# Interconnect.net
KiCad netlist of a schematic drawn in Altium Designer
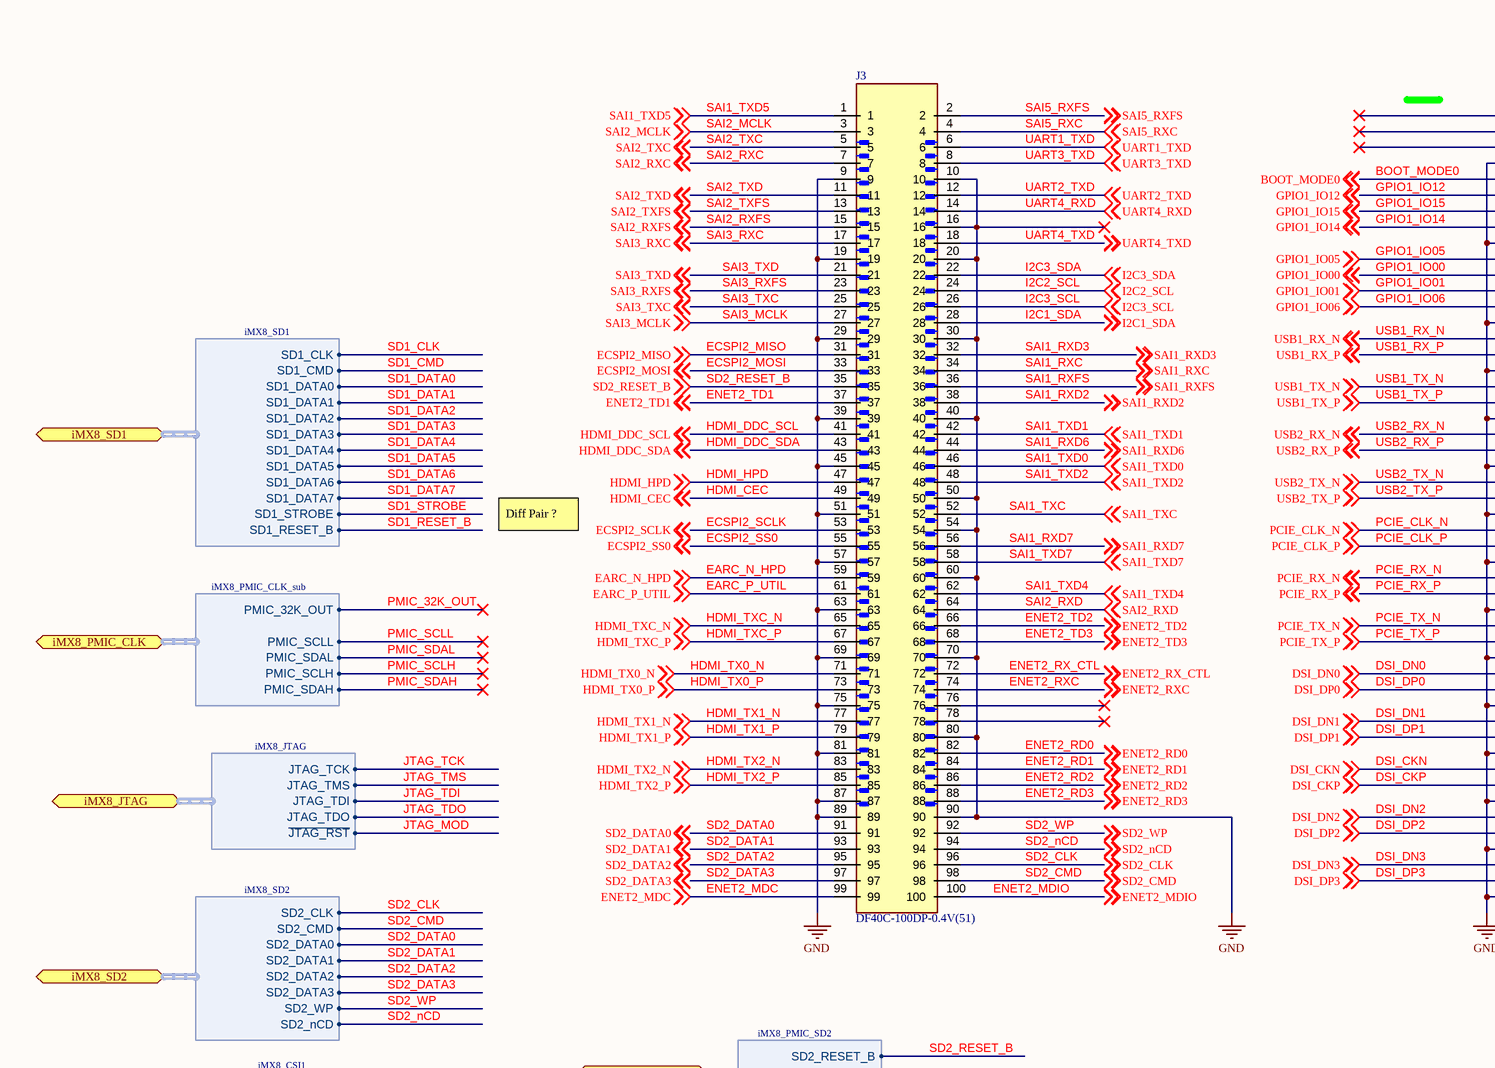
[diagram p0: Interconnect.SchDoc, top left]
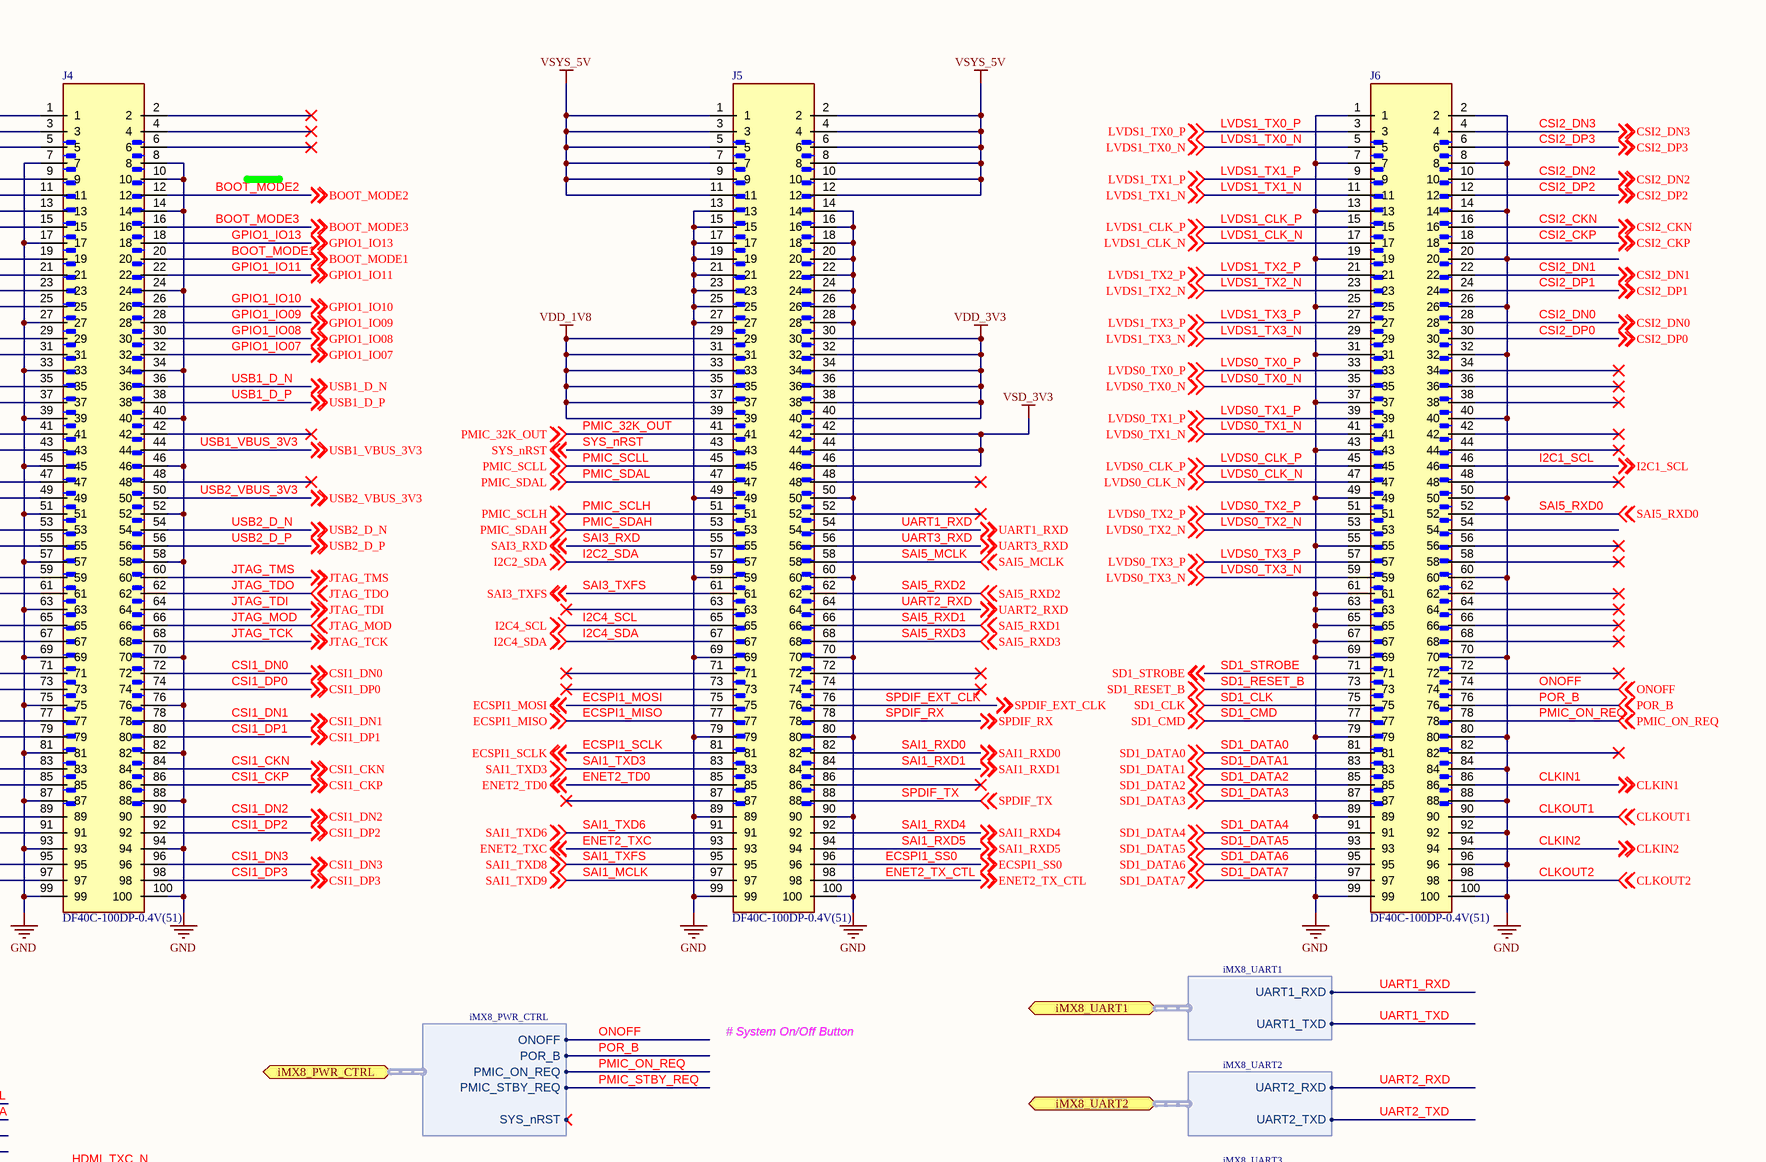
[diagram p1: Interconnect.SchDoc, top right]
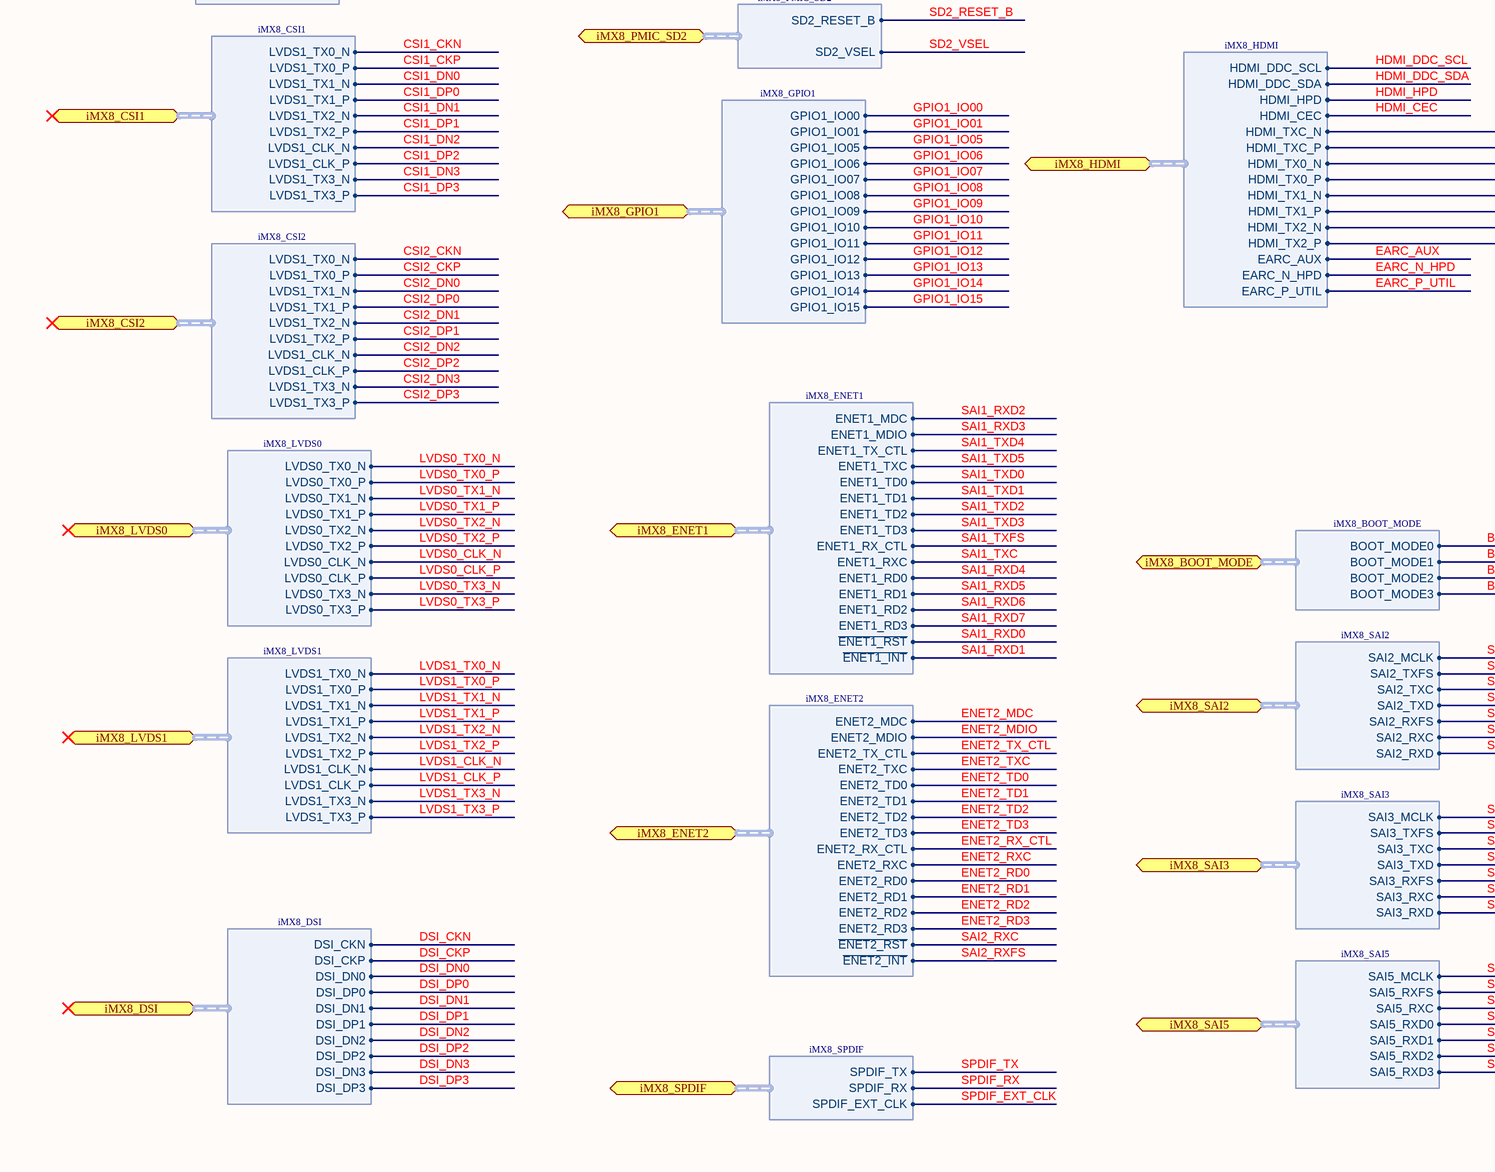
[diagram p2: Interconnect.SchDoc, bottom left]
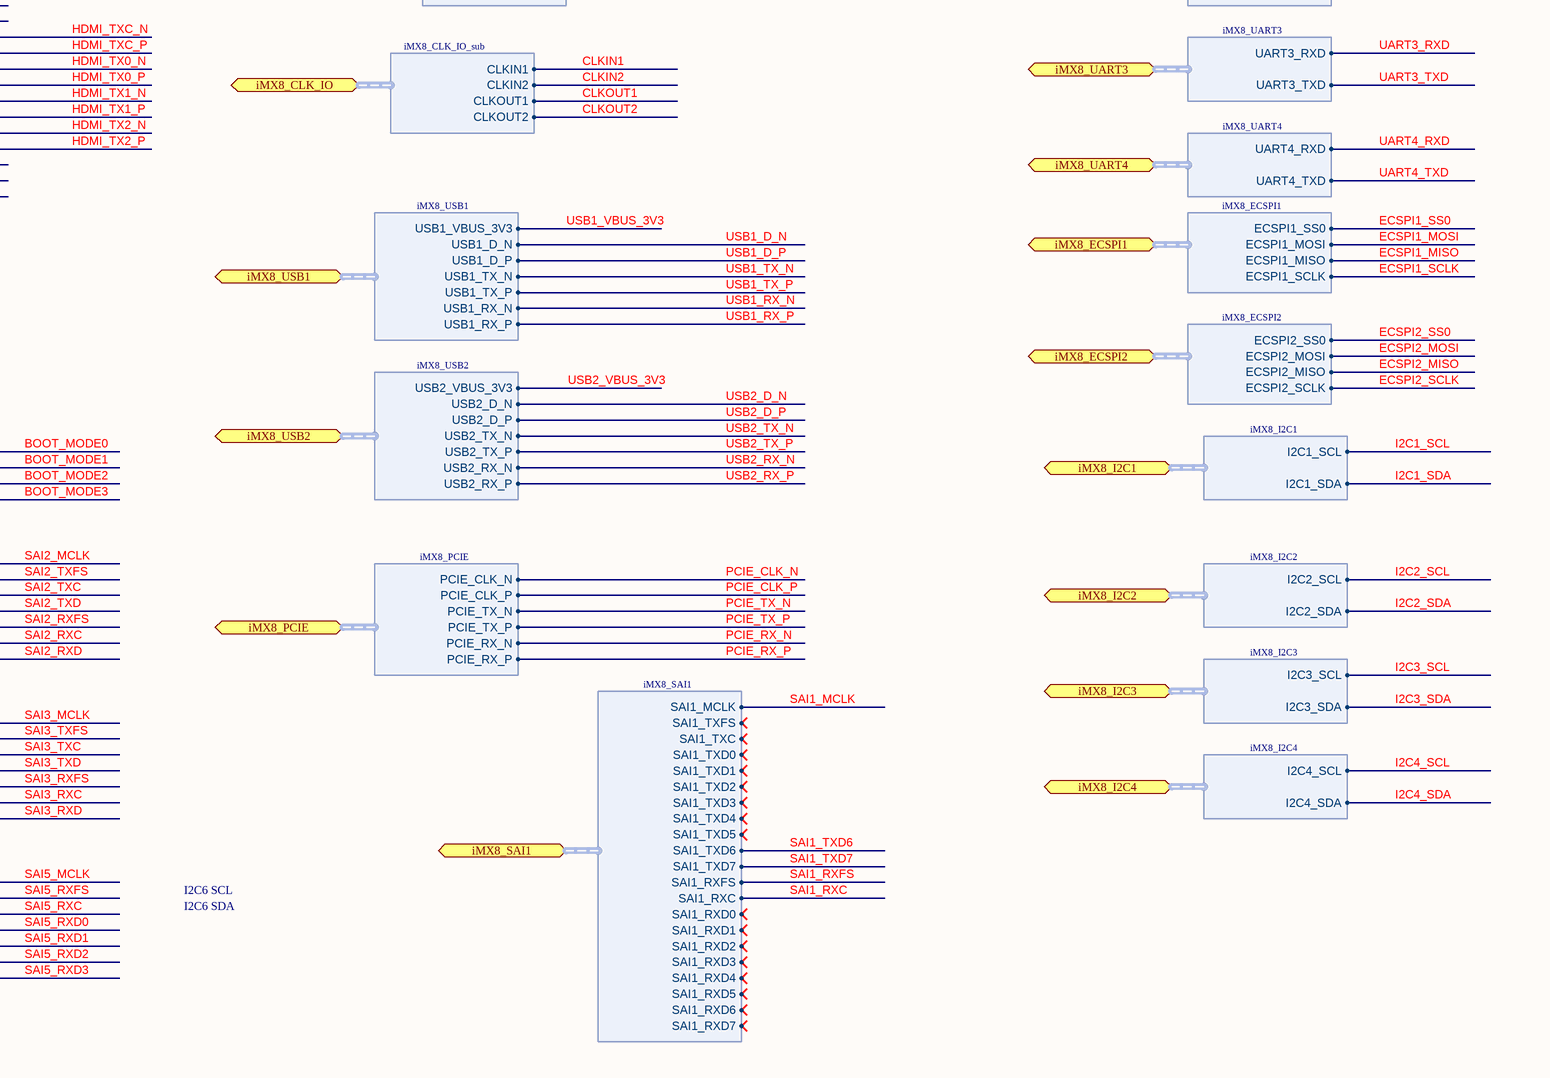
[diagram p3: Interconnect.SchDoc, bottom right]

(export (version "E")
  (design (tool "Eeschema 10.0.6"))
  (components
    (comp (ref "J3")
      (value "DF40C-100DP-0.4V(51)")
      (footprint "HIROSE_DF40C-100DP-0.4V(51)")
      (description "100 Position Connector Plug, Outer Shroud Contacts Surface Mount Gold")
      (fields (field (name "MF") "Hirose Electric"))
      (libsource (lib "DF40C-100DP-0.4V_51_") (part "DF40C-100DP-0.4V(51)"))
    )
    (comp (ref "J4")
      (value "DF40C-100DP-0.4V(51)")
      (footprint "HIROSE_DF40C-100DP-0.4V(51)")
      (description "100 Position Connector Plug, Outer Shroud Contacts Surface Mount Gold")
      (fields (field (name "MF") "Hirose Electric"))
      (libsource (lib "DF40C-100DP-0.4V_51_") (part "DF40C-100DP-0.4V(51)"))
    )
    (comp (ref "J5")
      (value "DF40C-100DP-0.4V(51)")
      (footprint "HIROSE_DF40C-100DP-0.4V(51)")
      (description "100 Position Connector Plug, Outer Shroud Contacts Surface Mount Gold")
      (fields (field (name "MF") "Hirose Electric"))
      (libsource (lib "DF40C-100DP-0.4V_51_") (part "DF40C-100DP-0.4V(51)"))
    )
    (comp (ref "J6")
      (value "DF40C-100DP-0.4V(51)")
      (footprint "HIROSE_DF40C-100DP-0.4V(51)")
      (description "100 Position Connector Plug, Outer Shroud Contacts Surface Mount Gold")
      (fields (field (name "MF") "Hirose Electric"))
      (libsource (lib "DF40C-100DP-0.4V_51_") (part "DF40C-100DP-0.4V(51)"))
    )
  )
  (nets
    (net (code "74") (name "BOOT_MODE0") (class "Default")
      (node (ref "J4") (pin "9") (pinfunction "9_9") (pintype "passive"))
    )
    (net (code "75") (name "BOOT_MODE1") (class "Default")
      (node (ref "J4") (pin "20") (pinfunction "20_20") (pintype "passive"))
    )
    (net (code "76") (name "BOOT_MODE2") (class "Default")
      (node (ref "J4") (pin "12") (pinfunction "12_12") (pintype "passive"))
    )
    (net (code "77") (name "BOOT_MODE3") (class "Default")
      (node (ref "J4") (pin "16") (pinfunction "16_16") (pintype "passive"))
    )
    (net (code "78") (name "CLKIN1") (class "Default")
      (node (ref "J6") (pin "86") (pinfunction "86_86") (pintype "passive"))
    )
    (net (code "79") (name "CLKIN2") (class "Default")
      (node (ref "J6") (pin "94") (pinfunction "94_94") (pintype "passive"))
    )
    (net (code "80") (name "CLKOUT1") (class "Default")
      (node (ref "J6") (pin "90") (pinfunction "90_90") (pintype "passive"))
    )
    (net (code "81") (name "CLKOUT2") (class "Default")
      (node (ref "J6") (pin "98") (pinfunction "98_98") (pintype "passive"))
    )
    (net (code "82") (name "CSI1_CKN") (class "Default")
      (node (ref "J4") (pin "84") (pinfunction "84_84") (pintype "passive"))
    )
    (net (code "83") (name "CSI1_CKP") (class "Default")
      (node (ref "J4") (pin "86") (pinfunction "86_86") (pintype "passive"))
    )
    (net (code "84") (name "CSI1_DN0") (class "Default")
      (node (ref "J4") (pin "72") (pinfunction "72_72") (pintype "passive"))
    )
    (net (code "85") (name "CSI1_DN1") (class "Default")
      (node (ref "J4") (pin "78") (pinfunction "78_78") (pintype "passive"))
    )
    (net (code "86") (name "CSI1_DN2") (class "Default")
      (node (ref "J4") (pin "90") (pinfunction "90_90") (pintype "passive"))
    )
    (net (code "87") (name "CSI1_DN3") (class "Default")
      (node (ref "J4") (pin "96") (pinfunction "96_96") (pintype "passive"))
    )
    (net (code "88") (name "CSI1_DP0") (class "Default")
      (node (ref "J4") (pin "74") (pinfunction "74_74") (pintype "passive"))
    )
    (net (code "89") (name "CSI1_DP1") (class "Default")
      (node (ref "J4") (pin "80") (pinfunction "80_80") (pintype "passive"))
    )
    (net (code "90") (name "CSI1_DP2") (class "Default")
      (node (ref "J4") (pin "92") (pinfunction "92_92") (pintype "passive"))
    )
    (net (code "91") (name "CSI1_DP3") (class "Default")
      (node (ref "J4") (pin "98") (pinfunction "98_98") (pintype "passive"))
    )
    (net (code "92") (name "CSI2_CKN") (class "Default")
      (node (ref "J6") (pin "16") (pinfunction "16_16") (pintype "passive"))
    )
    (net (code "93") (name "CSI2_CKP") (class "Default")
      (node (ref "J6") (pin "18") (pinfunction "18_18") (pintype "passive"))
    )
    (net (code "94") (name "CSI2_DN0") (class "Default")
      (node (ref "J6") (pin "28") (pinfunction "28_28") (pintype "passive"))
    )
    (net (code "95") (name "CSI2_DN1") (class "Default")
      (node (ref "J6") (pin "22") (pinfunction "22_22") (pintype "passive"))
    )
    (net (code "96") (name "CSI2_DN2") (class "Default")
      (node (ref "J6") (pin "10") (pinfunction "10_10") (pintype "passive"))
    )
    (net (code "97") (name "CSI2_DN3") (class "Default")
      (node (ref "J6") (pin "4") (pinfunction "4_4") (pintype "passive"))
    )
    (net (code "98") (name "CSI2_DP0") (class "Default")
      (node (ref "J6") (pin "30") (pinfunction "30_30") (pintype "passive"))
    )
    (net (code "99") (name "CSI2_DP1") (class "Default")
      (node (ref "J6") (pin "24") (pinfunction "24_24") (pintype "passive"))
    )
    (net (code "100") (name "CSI2_DP2") (class "Default")
      (node (ref "J6") (pin "12") (pinfunction "12_12") (pintype "passive"))
    )
    (net (code "101") (name "CSI2_DP3") (class "Default")
      (node (ref "J6") (pin "6") (pinfunction "6_6") (pintype "passive"))
    )
    (net (code "102") (name "DSI_CKN") (class "Default")
      (node (ref "J4") (pin "83") (pinfunction "83_83") (pintype "passive"))
    )
    (net (code "103") (name "DSI_CKP") (class "Default")
      (node (ref "J4") (pin "85") (pinfunction "85_85") (pintype "passive"))
    )
    (net (code "104") (name "DSI_DN0") (class "Default")
      (node (ref "J4") (pin "71") (pinfunction "71_71") (pintype "passive"))
    )
    (net (code "105") (name "DSI_DN1") (class "Default")
      (node (ref "J4") (pin "77") (pinfunction "77_77") (pintype "passive"))
    )
    (net (code "106") (name "DSI_DN2") (class "Default")
      (node (ref "J4") (pin "89") (pinfunction "89_89") (pintype "passive"))
    )
    (net (code "107") (name "DSI_DN3") (class "Default")
      (node (ref "J4") (pin "95") (pinfunction "95_95") (pintype "passive"))
    )
    (net (code "108") (name "DSI_DP0") (class "Default")
      (node (ref "J4") (pin "73") (pinfunction "73_73") (pintype "passive"))
    )
    (net (code "109") (name "DSI_DP1") (class "Default")
      (node (ref "J4") (pin "79") (pinfunction "79_79") (pintype "passive"))
    )
    (net (code "110") (name "DSI_DP2") (class "Default")
      (node (ref "J4") (pin "91") (pinfunction "91_91") (pintype "passive"))
    )
    (net (code "111") (name "DSI_DP3") (class "Default")
      (node (ref "J4") (pin "97") (pinfunction "97_97") (pintype "passive"))
    )
    (net (code "112") (name "EARC_N_HPD") (class "Default")
      (node (ref "J3") (pin "59") (pinfunction "59_59") (pintype "passive"))
    )
    (net (code "113") (name "EARC_P_UTIL") (class "Default")
      (node (ref "J3") (pin "61") (pinfunction "61_61") (pintype "passive"))
    )
    (net (code "114") (name "ECSPI1_MISO") (class "Default")
      (node (ref "J5") (pin "77") (pinfunction "77_77") (pintype "passive"))
    )
    (net (code "115") (name "ECSPI1_MOSI") (class "Default")
      (node (ref "J5") (pin "75") (pinfunction "75_75") (pintype "passive"))
    )
    (net (code "116") (name "ECSPI1_SCLK") (class "Default")
      (node (ref "J5") (pin "81") (pinfunction "81_81") (pintype "passive"))
    )
    (net (code "117") (name "ECSPI1_SS0") (class "Default")
      (node (ref "J5") (pin "96") (pinfunction "96_96") (pintype "passive"))
    )
    (net (code "118") (name "ECSPI2_MISO") (class "Default")
      (node (ref "J3") (pin "31") (pinfunction "31_31") (pintype "passive"))
    )
    (net (code "119") (name "ECSPI2_MOSI") (class "Default")
      (node (ref "J3") (pin "33") (pinfunction "33_33") (pintype "passive"))
    )
    (net (code "120") (name "ECSPI2_SCLK") (class "Default")
      (node (ref "J3") (pin "53") (pinfunction "53_53") (pintype "passive"))
    )
    (net (code "121") (name "ECSPI2_SS0") (class "Default")
      (node (ref "J3") (pin "55") (pinfunction "55_55") (pintype "passive"))
    )
    (net (code "122") (name "ENET2_MDC") (class "Default")
      (node (ref "J3") (pin "99") (pinfunction "99_99") (pintype "passive"))
    )
    (net (code "123") (name "ENET2_MDIO") (class "Default")
      (node (ref "J3") (pin "100") (pinfunction "100_100") (pintype "passive"))
    )
    (net (code "124") (name "ENET2_RD0") (class "Default")
      (node (ref "J3") (pin "82") (pinfunction "82_82") (pintype "passive"))
    )
    (net (code "125") (name "ENET2_RD1") (class "Default")
      (node (ref "J3") (pin "84") (pinfunction "84_84") (pintype "passive"))
    )
    (net (code "126") (name "ENET2_RD2") (class "Default")
      (node (ref "J3") (pin "86") (pinfunction "86_86") (pintype "passive"))
    )
    (net (code "127") (name "ENET2_RD3") (class "Default")
      (node (ref "J3") (pin "88") (pinfunction "88_88") (pintype "passive"))
    )
    (net (code "128") (name "ENET2_RXC") (class "Default")
      (node (ref "J3") (pin "74") (pinfunction "74_74") (pintype "passive"))
    )
    (net (code "129") (name "ENET2_RX_CTL") (class "Default")
      (node (ref "J3") (pin "72") (pinfunction "72_72") (pintype "passive"))
    )
    (net (code "130") (name "ENET2_TD0") (class "Default")
      (node (ref "J5") (pin "85") (pinfunction "85_85") (pintype "passive"))
    )
    (net (code "131") (name "ENET2_TD1") (class "Default")
      (node (ref "J3") (pin "37") (pinfunction "37_37") (pintype "passive"))
    )
    (net (code "132") (name "ENET2_TD2") (class "Default")
      (node (ref "J3") (pin "66") (pinfunction "66_66") (pintype "passive"))
    )
    (net (code "133") (name "ENET2_TD3") (class "Default")
      (node (ref "J3") (pin "68") (pinfunction "68_68") (pintype "passive"))
    )
    (net (code "134") (name "ENET2_TXC") (class "Default")
      (node (ref "J5") (pin "93") (pinfunction "93_93") (pintype "passive"))
    )
    (net (code "135") (name "ENET2_TX_CTL") (class "Default")
      (node (ref "J5") (pin "98") (pinfunction "98_98") (pintype "passive"))
    )
    (net (code "136") (name "GND") (class "Default")
      (node (ref "J3") (pin "10") (pinfunction "10_10") (pintype "passive"))
      (node (ref "J3") (pin "16") (pinfunction "16_16") (pintype "passive"))
      (node (ref "J3") (pin "19") (pinfunction "19_19") (pintype "passive"))
      (node (ref "J3") (pin "20") (pinfunction "20_20") (pintype "passive"))
      (node (ref "J3") (pin "29") (pinfunction "29_29") (pintype "passive"))
      (node (ref "J3") (pin "30") (pinfunction "30_30") (pintype "passive"))
      (node (ref "J3") (pin "39") (pinfunction "39_39") (pintype "passive"))
      (node (ref "J3") (pin "40") (pinfunction "40_40") (pintype "passive"))
      (node (ref "J3") (pin "45") (pinfunction "45_45") (pintype "passive"))
      (node (ref "J3") (pin "50") (pinfunction "50_50") (pintype "passive"))
      (node (ref "J3") (pin "51") (pinfunction "51_51") (pintype "passive"))
      (node (ref "J3") (pin "54") (pinfunction "54_54") (pintype "passive"))
      (node (ref "J3") (pin "57") (pinfunction "57_57") (pintype "passive"))
      (node (ref "J3") (pin "60") (pinfunction "60_60") (pintype "passive"))
      (node (ref "J3") (pin "63") (pinfunction "63_63") (pintype "passive"))
      (node (ref "J3") (pin "69") (pinfunction "69_69") (pintype "passive"))
      (node (ref "J3") (pin "70") (pinfunction "70_70") (pintype "passive"))
      (node (ref "J3") (pin "75") (pinfunction "75_75") (pintype "passive"))
      (node (ref "J3") (pin "80") (pinfunction "80_80") (pintype "passive"))
      (node (ref "J3") (pin "81") (pinfunction "81_81") (pintype "passive"))
      (node (ref "J3") (pin "87") (pinfunction "87_87") (pintype "passive"))
      (node (ref "J3") (pin "89") (pinfunction "89_89") (pintype "passive"))
      (node (ref "J3") (pin "9") (pinfunction "9_9") (pintype "passive"))
      (node (ref "J3") (pin "90") (pinfunction "90_90") (pintype "passive"))
      (node (ref "J4") (pin "10") (pinfunction "10_10") (pintype "passive"))
      (node (ref "J4") (pin "100") (pinfunction "100_100") (pintype "passive"))
      (node (ref "J4") (pin "14") (pinfunction "14_14") (pintype "passive"))
      (node (ref "J4") (pin "17") (pinfunction "17_17") (pintype "passive"))
      (node (ref "J4") (pin "24") (pinfunction "24_24") (pintype "passive"))
      (node (ref "J4") (pin "27") (pinfunction "27_27") (pintype "passive"))
      (node (ref "J4") (pin "33") (pinfunction "33_33") (pintype "passive"))
      (node (ref "J4") (pin "34") (pinfunction "34_34") (pintype "passive"))
      (node (ref "J4") (pin "39") (pinfunction "39_39") (pintype "passive"))
      (node (ref "J4") (pin "40") (pinfunction "40_40") (pintype "passive"))
      (node (ref "J4") (pin "45") (pinfunction "45_45") (pintype "passive"))
      (node (ref "J4") (pin "46") (pinfunction "46_46") (pintype "passive"))
      (node (ref "J4") (pin "51") (pinfunction "51_51") (pintype "passive"))
      (node (ref "J4") (pin "52") (pinfunction "52_52") (pintype "passive"))
      (node (ref "J4") (pin "57") (pinfunction "57_57") (pintype "passive"))
      (node (ref "J4") (pin "58") (pinfunction "58_58") (pintype "passive"))
      (node (ref "J4") (pin "63") (pinfunction "63_63") (pintype "passive"))
      (node (ref "J4") (pin "69") (pinfunction "69_69") (pintype "passive"))
      (node (ref "J4") (pin "7") (pinfunction "7_7") (pintype "passive"))
      (node (ref "J4") (pin "70") (pinfunction "70_70") (pintype "passive"))
      (node (ref "J4") (pin "75") (pinfunction "75_75") (pintype "passive"))
      (node (ref "J4") (pin "76") (pinfunction "76_76") (pintype "passive"))
      (node (ref "J4") (pin "8") (pinfunction "8_8") (pintype "passive"))
      (node (ref "J4") (pin "81") (pinfunction "81_81") (pintype "passive"))
      (node (ref "J4") (pin "82") (pinfunction "82_82") (pintype "passive"))
      (node (ref "J4") (pin "87") (pinfunction "87_87") (pintype "passive"))
      (node (ref "J4") (pin "88") (pinfunction "88_88") (pintype "passive"))
      (node (ref "J4") (pin "93") (pinfunction "93_93") (pintype "passive"))
      (node (ref "J4") (pin "94") (pinfunction "94_94") (pintype "passive"))
      (node (ref "J4") (pin "99") (pinfunction "99_99") (pintype "passive"))
      (node (ref "J5") (pin "100") (pinfunction "100_100") (pintype "passive"))
      (node (ref "J5") (pin "13") (pinfunction "13_13") (pintype "passive"))
      (node (ref "J5") (pin "14") (pinfunction "14_14") (pintype "passive"))
      (node (ref "J5") (pin "15") (pinfunction "15_15") (pintype "passive"))
      (node (ref "J5") (pin "16") (pinfunction "16_16") (pintype "passive"))
      (node (ref "J5") (pin "17") (pinfunction "17_17") (pintype "passive"))
      (node (ref "J5") (pin "18") (pinfunction "18_18") (pintype "passive"))
      (node (ref "J5") (pin "19") (pinfunction "19_19") (pintype "passive"))
      (node (ref "J5") (pin "20") (pinfunction "20_20") (pintype "passive"))
      (node (ref "J5") (pin "21") (pinfunction "21_21") (pintype "passive"))
      (node (ref "J5") (pin "22") (pinfunction "22_22") (pintype "passive"))
      (node (ref "J5") (pin "23") (pinfunction "23_23") (pintype "passive"))
      (node (ref "J5") (pin "24") (pinfunction "24_24") (pintype "passive"))
      (node (ref "J5") (pin "25") (pinfunction "25_25") (pintype "passive"))
      (node (ref "J5") (pin "26") (pinfunction "26_26") (pintype "passive"))
      (node (ref "J5") (pin "27") (pinfunction "27_27") (pintype "passive"))
      (node (ref "J5") (pin "28") (pinfunction "28_28") (pintype "passive"))
      (node (ref "J5") (pin "49") (pinfunction "49_49") (pintype "passive"))
      (node (ref "J5") (pin "50") (pinfunction "50_50") (pintype "passive"))
      (node (ref "J5") (pin "59") (pinfunction "59_59") (pintype "passive"))
      (node (ref "J5") (pin "60") (pinfunction "60_60") (pintype "passive"))
      (node (ref "J5") (pin "69") (pinfunction "69_69") (pintype "passive"))
      (node (ref "J5") (pin "70") (pinfunction "70_70") (pintype "passive"))
      (node (ref "J5") (pin "79") (pinfunction "79_79") (pintype "passive"))
      (node (ref "J5") (pin "80") (pinfunction "80_80") (pintype "passive"))
      (node (ref "J5") (pin "89") (pinfunction "89_89") (pintype "passive"))
      (node (ref "J5") (pin "90") (pinfunction "90_90") (pintype "passive"))
      (node (ref "J5") (pin "99") (pinfunction "99_99") (pintype "passive"))
      (node (ref "J6") (pin "1") (pinfunction "1_1") (pintype "passive"))
      (node (ref "J6") (pin "100") (pinfunction "100_100") (pintype "passive"))
      (node (ref "J6") (pin "13") (pinfunction "13_13") (pintype "passive"))
      (node (ref "J6") (pin "14") (pinfunction "14_14") (pintype "passive"))
      (node (ref "J6") (pin "19") (pinfunction "19_19") (pintype "passive"))
      (node (ref "J6") (pin "2") (pinfunction "2_2") (pintype "passive"))
      (node (ref "J6") (pin "20") (pinfunction "20_20") (pintype "passive"))
      (node (ref "J6") (pin "25") (pinfunction "25_25") (pintype "passive"))
      (node (ref "J6") (pin "26") (pinfunction "26_26") (pintype "passive"))
      (node (ref "J6") (pin "31") (pinfunction "31_31") (pintype "passive"))
      (node (ref "J6") (pin "32") (pinfunction "32_32") (pintype "passive"))
      (node (ref "J6") (pin "37") (pinfunction "37_37") (pintype "passive"))
      (node (ref "J6") (pin "40") (pinfunction "40_40") (pintype "passive"))
      (node (ref "J6") (pin "43") (pinfunction "43_43") (pintype "passive"))
      (node (ref "J6") (pin "49") (pinfunction "49_49") (pintype "passive"))
      (node (ref "J6") (pin "50") (pinfunction "50_50") (pintype "passive"))
      (node (ref "J6") (pin "55") (pinfunction "55_55") (pintype "passive"))
      (node (ref "J6") (pin "60") (pinfunction "60_60") (pintype "passive"))
      (node (ref "J6") (pin "61") (pinfunction "61_61") (pintype "passive"))
      (node (ref "J6") (pin "63") (pinfunction "63_63") (pintype "passive"))
      (node (ref "J6") (pin "65") (pinfunction "65_65") (pintype "passive"))
      (node (ref "J6") (pin "67") (pinfunction "67_67") (pintype "passive"))
      (node (ref "J6") (pin "69") (pinfunction "69_69") (pintype "passive"))
      (node (ref "J6") (pin "7") (pinfunction "7_7") (pintype "passive"))
      (node (ref "J6") (pin "70") (pinfunction "70_70") (pintype "passive"))
      (node (ref "J6") (pin "79") (pinfunction "79_79") (pintype "passive"))
      (node (ref "J6") (pin "8") (pinfunction "8_8") (pintype "passive"))
      (node (ref "J6") (pin "80") (pinfunction "80_80") (pintype "passive"))
      (node (ref "J6") (pin "84") (pinfunction "84_84") (pintype "passive"))
      (node (ref "J6") (pin "88") (pinfunction "88_88") (pintype "passive"))
      (node (ref "J6") (pin "89") (pinfunction "89_89") (pintype "passive"))
      (node (ref "J6") (pin "92") (pinfunction "92_92") (pintype "passive"))
      (node (ref "J6") (pin "96") (pinfunction "96_96") (pintype "passive"))
      (node (ref "J6") (pin "99") (pinfunction "99_99") (pintype "passive"))
    )
    (net (code "137") (name "GPIO1_IO00") (class "Default")
      (node (ref "J4") (pin "21") (pinfunction "21_21") (pintype "passive"))
    )
    (net (code "138") (name "GPIO1_IO01") (class "Default")
      (node (ref "J4") (pin "23") (pinfunction "23_23") (pintype "passive"))
    )
    (net (code "139") (name "GPIO1_IO05") (class "Default")
      (node (ref "J4") (pin "19") (pinfunction "19_19") (pintype "passive"))
    )
    (net (code "140") (name "GPIO1_IO06") (class "Default")
      (node (ref "J4") (pin "25") (pinfunction "25_25") (pintype "passive"))
    )
    (net (code "141") (name "GPIO1_IO07") (class "Default")
      (node (ref "J4") (pin "32") (pinfunction "32_32") (pintype "passive"))
    )
    (net (code "142") (name "GPIO1_IO08") (class "Default")
      (node (ref "J4") (pin "30") (pinfunction "30_30") (pintype "passive"))
    )
    (net (code "143") (name "GPIO1_IO09") (class "Default")
      (node (ref "J4") (pin "28") (pinfunction "28_28") (pintype "passive"))
    )
    (net (code "144") (name "GPIO1_IO10") (class "Default")
      (node (ref "J4") (pin "26") (pinfunction "26_26") (pintype "passive"))
    )
    (net (code "145") (name "GPIO1_IO11") (class "Default")
      (node (ref "J4") (pin "22") (pinfunction "22_22") (pintype "passive"))
    )
    (net (code "146") (name "GPIO1_IO12") (class "Default")
      (node (ref "J4") (pin "11") (pinfunction "11_11") (pintype "passive"))
    )
    (net (code "147") (name "GPIO1_IO13") (class "Default")
      (node (ref "J4") (pin "18") (pinfunction "18_18") (pintype "passive"))
    )
    (net (code "148") (name "GPIO1_IO14") (class "Default")
      (node (ref "J4") (pin "15") (pinfunction "15_15") (pintype "passive"))
    )
    (net (code "149") (name "GPIO1_IO15") (class "Default")
      (node (ref "J4") (pin "13") (pinfunction "13_13") (pintype "passive"))
    )
    (net (code "150") (name "HDMI_CEC") (class "Default")
      (node (ref "J3") (pin "49") (pinfunction "49_49") (pintype "passive"))
    )
    (net (code "151") (name "HDMI_DDC_SCL") (class "Default")
      (node (ref "J3") (pin "41") (pinfunction "41_41") (pintype "passive"))
    )
    (net (code "152") (name "HDMI_DDC_SDA") (class "Default")
      (node (ref "J3") (pin "43") (pinfunction "43_43") (pintype "passive"))
    )
    (net (code "153") (name "HDMI_HPD") (class "Default")
      (node (ref "J3") (pin "47") (pinfunction "47_47") (pintype "passive"))
    )
    (net (code "154") (name "HDMI_TX0_N") (class "Default")
      (node (ref "J3") (pin "71") (pinfunction "71_71") (pintype "passive"))
    )
    (net (code "155") (name "HDMI_TX0_P") (class "Default")
      (node (ref "J3") (pin "73") (pinfunction "73_73") (pintype "passive"))
    )
    (net (code "156") (name "HDMI_TX1_N") (class "Default")
      (node (ref "J3") (pin "77") (pinfunction "77_77") (pintype "passive"))
    )
    (net (code "157") (name "HDMI_TX1_P") (class "Default")
      (node (ref "J3") (pin "79") (pinfunction "79_79") (pintype "passive"))
    )
    (net (code "158") (name "HDMI_TX2_N") (class "Default")
      (node (ref "J3") (pin "83") (pinfunction "83_83") (pintype "passive"))
    )
    (net (code "159") (name "HDMI_TX2_P") (class "Default")
      (node (ref "J3") (pin "85") (pinfunction "85_85") (pintype "passive"))
    )
    (net (code "160") (name "HDMI_TXC_N") (class "Default")
      (node (ref "J3") (pin "65") (pinfunction "65_65") (pintype "passive"))
    )
    (net (code "161") (name "HDMI_TXC_P") (class "Default")
      (node (ref "J3") (pin "67") (pinfunction "67_67") (pintype "passive"))
    )
    (net (code "162") (name "I2C1_SCL") (class "Default")
      (node (ref "J6") (pin "46") (pinfunction "46_46") (pintype "passive"))
    )
    (net (code "163") (name "I2C1_SDA") (class "Default")
      (node (ref "J3") (pin "28") (pinfunction "28_28") (pintype "passive"))
    )
    (net (code "164") (name "I2C2_SCL") (class "Default")
      (node (ref "J3") (pin "24") (pinfunction "24_24") (pintype "passive"))
    )
    (net (code "165") (name "I2C2_SDA") (class "Default")
      (node (ref "J5") (pin "57") (pinfunction "57_57") (pintype "passive"))
    )
    (net (code "166") (name "I2C3_SCL") (class "Default")
      (node (ref "J3") (pin "26") (pinfunction "26_26") (pintype "passive"))
    )
    (net (code "167") (name "I2C3_SDA") (class "Default")
      (node (ref "J3") (pin "22") (pinfunction "22_22") (pintype "passive"))
    )
    (net (code "168") (name "I2C4_SCL") (class "Default")
      (node (ref "J5") (pin "65") (pinfunction "65_65") (pintype "passive"))
    )
    (net (code "169") (name "I2C4_SDA") (class "Default")
      (node (ref "J5") (pin "67") (pinfunction "67_67") (pintype "passive"))
    )
    (net (code "170") (name "JTAG_MOD") (class "Default")
      (node (ref "J4") (pin "66") (pinfunction "66_66") (pintype "passive"))
    )
    (net (code "171") (name "JTAG_TCK") (class "Default")
      (node (ref "J4") (pin "68") (pinfunction "68_68") (pintype "passive"))
    )
    (net (code "172") (name "JTAG_TDI") (class "Default")
      (node (ref "J4") (pin "64") (pinfunction "64_64") (pintype "passive"))
    )
    (net (code "173") (name "JTAG_TDO") (class "Default")
      (node (ref "J4") (pin "62") (pinfunction "62_62") (pintype "passive"))
    )
    (net (code "174") (name "JTAG_TMS") (class "Default")
      (node (ref "J4") (pin "60") (pinfunction "60_60") (pintype "passive"))
    )
    (net (code "175") (name "LVDS0_CLK_N") (class "Default")
      (node (ref "J6") (pin "47") (pinfunction "47_47") (pintype "passive"))
    )
    (net (code "176") (name "LVDS0_CLK_P") (class "Default")
      (node (ref "J6") (pin "45") (pinfunction "45_45") (pintype "passive"))
    )
    (net (code "177") (name "LVDS0_TX0_N") (class "Default")
      (node (ref "J6") (pin "35") (pinfunction "35_35") (pintype "passive"))
    )
    (net (code "178") (name "LVDS0_TX0_P") (class "Default")
      (node (ref "J6") (pin "33") (pinfunction "33_33") (pintype "passive"))
    )
    (net (code "179") (name "LVDS0_TX1_N") (class "Default")
      (node (ref "J6") (pin "41") (pinfunction "41_41") (pintype "passive"))
    )
    (net (code "180") (name "LVDS0_TX1_P") (class "Default")
      (node (ref "J6") (pin "39") (pinfunction "39_39") (pintype "passive"))
    )
    (net (code "181") (name "LVDS0_TX2_N") (class "Default")
      (node (ref "J6") (pin "53") (pinfunction "53_53") (pintype "passive"))
    )
    (net (code "182") (name "LVDS0_TX2_P") (class "Default")
      (node (ref "J6") (pin "51") (pinfunction "51_51") (pintype "passive"))
    )
    (net (code "183") (name "LVDS0_TX3_N") (class "Default")
      (node (ref "J6") (pin "59") (pinfunction "59_59") (pintype "passive"))
    )
    (net (code "184") (name "LVDS0_TX3_P") (class "Default")
      (node (ref "J6") (pin "57") (pinfunction "57_57") (pintype "passive"))
    )
    (net (code "185") (name "LVDS1_CLK_N") (class "Default")
      (node (ref "J6") (pin "17") (pinfunction "17_17") (pintype "passive"))
    )
    (net (code "186") (name "LVDS1_CLK_P") (class "Default")
      (node (ref "J6") (pin "15") (pinfunction "15_15") (pintype "passive"))
    )
    (net (code "187") (name "LVDS1_TX0_N") (class "Default")
      (node (ref "J6") (pin "5") (pinfunction "5_5") (pintype "passive"))
    )
    (net (code "188") (name "LVDS1_TX0_P") (class "Default")
      (node (ref "J6") (pin "3") (pinfunction "3_3") (pintype "passive"))
    )
    (net (code "189") (name "LVDS1_TX1_N") (class "Default")
      (node (ref "J6") (pin "11") (pinfunction "11_11") (pintype "passive"))
    )
    (net (code "190") (name "LVDS1_TX1_P") (class "Default")
      (node (ref "J6") (pin "9") (pinfunction "9_9") (pintype "passive"))
    )
    (net (code "191") (name "LVDS1_TX2_N") (class "Default")
      (node (ref "J6") (pin "23") (pinfunction "23_23") (pintype "passive"))
    )
    (net (code "192") (name "LVDS1_TX2_P") (class "Default")
      (node (ref "J6") (pin "21") (pinfunction "21_21") (pintype "passive"))
    )
    (net (code "193") (name "LVDS1_TX3_N") (class "Default")
      (node (ref "J6") (pin "29") (pinfunction "29_29") (pintype "passive"))
    )
    (net (code "194") (name "LVDS1_TX3_P") (class "Default")
      (node (ref "J6") (pin "27") (pinfunction "27_27") (pintype "passive"))
    )
    (net (code "195") (name "ONOFF") (class "Default")
      (node (ref "J6") (pin "74") (pinfunction "74_74") (pintype "passive"))
    )
    (net (code "196") (name "PCIE_CLK_N") (class "Default")
      (node (ref "J4") (pin "53") (pinfunction "53_53") (pintype "passive"))
    )
    (net (code "197") (name "PCIE_CLK_P") (class "Default")
      (node (ref "J4") (pin "55") (pinfunction "55_55") (pintype "passive"))
    )
    (net (code "198") (name "PCIE_RX_N") (class "Default")
      (node (ref "J4") (pin "59") (pinfunction "59_59") (pintype "passive"))
    )
    (net (code "199") (name "PCIE_RX_P") (class "Default")
      (node (ref "J4") (pin "61") (pinfunction "61_61") (pintype "passive"))
    )
    (net (code "200") (name "PCIE_TX_N") (class "Default")
      (node (ref "J4") (pin "65") (pinfunction "65_65") (pintype "passive"))
    )
    (net (code "201") (name "PCIE_TX_P") (class "Default")
      (node (ref "J4") (pin "67") (pinfunction "67_67") (pintype "passive"))
    )
    (net (code "202") (name "PMIC_32K_OUT") (class "Default")
      (node (ref "J5") (pin "41") (pinfunction "41_41") (pintype "passive"))
    )
    (net (code "203") (name "PMIC_ON_REQ") (class "Default")
      (node (ref "J6") (pin "78") (pinfunction "78_78") (pintype "passive"))
    )
    (net (code "204") (name "PMIC_SCLH") (class "Default")
      (node (ref "J5") (pin "51") (pinfunction "51_51") (pintype "passive"))
    )
    (net (code "205") (name "PMIC_SCLL") (class "Default")
      (node (ref "J5") (pin "45") (pinfunction "45_45") (pintype "passive"))
    )
    (net (code "206") (name "PMIC_SDAH") (class "Default")
      (node (ref "J5") (pin "53") (pinfunction "53_53") (pintype "passive"))
    )
    (net (code "207") (name "PMIC_SDAL") (class "Default")
      (node (ref "J5") (pin "47") (pinfunction "47_47") (pintype "passive"))
    )
    (net (code "208") (name "POR_B") (class "Default")
      (node (ref "J6") (pin "76") (pinfunction "76_76") (pintype "passive"))
    )
    (net (code "209") (name "SAI1_RXC") (class "Default")
      (node (ref "J3") (pin "34") (pinfunction "34_34") (pintype "passive"))
    )
    (net (code "210") (name "SAI1_RXD0") (class "Default")
      (node (ref "J5") (pin "82") (pinfunction "82_82") (pintype "passive"))
    )
    (net (code "211") (name "SAI1_RXD1") (class "Default")
      (node (ref "J5") (pin "84") (pinfunction "84_84") (pintype "passive"))
    )
    (net (code "212") (name "SAI1_RXD2") (class "Default")
      (node (ref "J3") (pin "38") (pinfunction "38_38") (pintype "passive"))
    )
    (net (code "213") (name "SAI1_RXD3") (class "Default")
      (node (ref "J3") (pin "32") (pinfunction "32_32") (pintype "passive"))
    )
    (net (code "214") (name "SAI1_RXD4") (class "Default")
      (node (ref "J5") (pin "92") (pinfunction "92_92") (pintype "passive"))
    )
    (net (code "215") (name "SAI1_RXD5") (class "Default")
      (node (ref "J5") (pin "94") (pinfunction "94_94") (pintype "passive"))
    )
    (net (code "216") (name "SAI1_RXD6") (class "Default")
      (node (ref "J3") (pin "44") (pinfunction "44_44") (pintype "passive"))
    )
    (net (code "217") (name "SAI1_RXD7") (class "Default")
      (node (ref "J3") (pin "56") (pinfunction "56_56") (pintype "passive"))
    )
    (net (code "218") (name "SAI1_RXFS") (class "Default")
      (node (ref "J3") (pin "36") (pinfunction "36_36") (pintype "passive"))
    )
    (net (code "219") (name "SAI1_TXC") (class "Default")
      (node (ref "J3") (pin "52") (pinfunction "52_52") (pintype "passive"))
    )
    (net (code "220") (name "SAI1_TXD0") (class "Default")
      (node (ref "J3") (pin "46") (pinfunction "46_46") (pintype "passive"))
    )
    (net (code "221") (name "SAI1_TXD1") (class "Default")
      (node (ref "J3") (pin "42") (pinfunction "42_42") (pintype "passive"))
    )
    (net (code "222") (name "SAI1_TXD2") (class "Default")
      (node (ref "J3") (pin "48") (pinfunction "48_48") (pintype "passive"))
    )
    (net (code "223") (name "SAI1_TXD3") (class "Default")
      (node (ref "J5") (pin "83") (pinfunction "83_83") (pintype "passive"))
    )
    (net (code "224") (name "SAI1_TXD4") (class "Default")
      (node (ref "J3") (pin "62") (pinfunction "62_62") (pintype "passive"))
    )
    (net (code "225") (name "SAI1_TXD5") (class "Default")
      (node (ref "J3") (pin "1") (pinfunction "1_1") (pintype "passive"))
    )
    (net (code "226") (name "SAI1_TXD6") (class "Default")
      (node (ref "J5") (pin "91") (pinfunction "91_91") (pintype "passive"))
    )
    (net (code "227") (name "SAI1_TXD7") (class "Default")
      (node (ref "J3") (pin "58") (pinfunction "58_58") (pintype "passive"))
    )
    (net (code "228") (name "SAI1_TXD8") (class "Default")
      (node (ref "J5") (pin "95") (pinfunction "95_95") (pintype "passive"))
    )
    (net (code "229") (name "SAI1_TXD9") (class "Default")
      (node (ref "J5") (pin "97") (pinfunction "97_97") (pintype "passive"))
    )
    (net (code "230") (name "SAI2_MCLK") (class "Default")
      (node (ref "J3") (pin "3") (pinfunction "3_3") (pintype "passive"))
    )
    (net (code "231") (name "SAI2_RXC") (class "Default")
      (node (ref "J3") (pin "7") (pinfunction "7_7") (pintype "passive"))
    )
    (net (code "232") (name "SAI2_RXD") (class "Default")
      (node (ref "J3") (pin "64") (pinfunction "64_64") (pintype "passive"))
    )
    (net (code "233") (name "SAI2_RXFS") (class "Default")
      (node (ref "J3") (pin "15") (pinfunction "15_15") (pintype "passive"))
    )
    (net (code "234") (name "SAI2_TXC") (class "Default")
      (node (ref "J3") (pin "5") (pinfunction "5_5") (pintype "passive"))
    )
    (net (code "235") (name "SAI2_TXD") (class "Default")
      (node (ref "J3") (pin "11") (pinfunction "11_11") (pintype "passive"))
    )
    (net (code "236") (name "SAI2_TXFS") (class "Default")
      (node (ref "J3") (pin "13") (pinfunction "13_13") (pintype "passive"))
    )
    (net (code "237") (name "SAI3_MCLK") (class "Default")
      (node (ref "J3") (pin "27") (pinfunction "27_27") (pintype "passive"))
    )
    (net (code "238") (name "SAI3_RXC") (class "Default")
      (node (ref "J3") (pin "17") (pinfunction "17_17") (pintype "passive"))
    )
    (net (code "239") (name "SAI3_RXD") (class "Default")
      (node (ref "J5") (pin "55") (pinfunction "55_55") (pintype "passive"))
    )
    (net (code "240") (name "SAI3_RXFS") (class "Default")
      (node (ref "J3") (pin "23") (pinfunction "23_23") (pintype "passive"))
    )
    (net (code "241") (name "SAI3_TXC") (class "Default")
      (node (ref "J3") (pin "25") (pinfunction "25_25") (pintype "passive"))
    )
    (net (code "242") (name "SAI3_TXD") (class "Default")
      (node (ref "J3") (pin "21") (pinfunction "21_21") (pintype "passive"))
    )
    (net (code "243") (name "SAI3_TXFS") (class "Default")
      (node (ref "J5") (pin "61") (pinfunction "61_61") (pintype "passive"))
    )
    (net (code "244") (name "SAI5_MCLK") (class "Default")
      (node (ref "J5") (pin "58") (pinfunction "58_58") (pintype "passive"))
    )
    (net (code "245") (name "SAI5_RXC") (class "Default")
      (node (ref "J3") (pin "4") (pinfunction "4_4") (pintype "passive"))
    )
    (net (code "246") (name "SAI5_RXD0") (class "Default")
      (node (ref "J6") (pin "52") (pinfunction "52_52") (pintype "passive"))
    )
    (net (code "247") (name "SAI5_RXD1") (class "Default")
      (node (ref "J5") (pin "66") (pinfunction "66_66") (pintype "passive"))
    )
    (net (code "248") (name "SAI5_RXD2") (class "Default")
      (node (ref "J5") (pin "62") (pinfunction "62_62") (pintype "passive"))
    )
    (net (code "249") (name "SAI5_RXD3") (class "Default")
      (node (ref "J5") (pin "68") (pinfunction "68_68") (pintype "passive"))
    )
    (net (code "250") (name "SAI5_RXFS") (class "Default")
      (node (ref "J3") (pin "2") (pinfunction "2_2") (pintype "passive"))
    )
    (net (code "251") (name "SD1_CLK") (class "Default")
      (node (ref "J6") (pin "75") (pinfunction "75_75") (pintype "passive"))
    )
    (net (code "252") (name "SD1_CMD") (class "Default")
      (node (ref "J6") (pin "77") (pinfunction "77_77") (pintype "passive"))
    )
    (net (code "253") (name "SD1_DATA0") (class "Default")
      (node (ref "J6") (pin "81") (pinfunction "81_81") (pintype "passive"))
    )
    (net (code "254") (name "SD1_DATA1") (class "Default")
      (node (ref "J6") (pin "83") (pinfunction "83_83") (pintype "passive"))
    )
    (net (code "255") (name "SD1_DATA2") (class "Default")
      (node (ref "J6") (pin "85") (pinfunction "85_85") (pintype "passive"))
    )
    (net (code "256") (name "SD1_DATA3") (class "Default")
      (node (ref "J6") (pin "87") (pinfunction "87_87") (pintype "passive"))
    )
    (net (code "257") (name "SD1_DATA4") (class "Default")
      (node (ref "J6") (pin "91") (pinfunction "91_91") (pintype "passive"))
    )
    (net (code "258") (name "SD1_DATA5") (class "Default")
      (node (ref "J6") (pin "93") (pinfunction "93_93") (pintype "passive"))
    )
    (net (code "259") (name "SD1_DATA6") (class "Default")
      (node (ref "J6") (pin "95") (pinfunction "95_95") (pintype "passive"))
    )
    (net (code "260") (name "SD1_DATA7") (class "Default")
      (node (ref "J6") (pin "97") (pinfunction "97_97") (pintype "passive"))
    )
    (net (code "261") (name "SD1_RESET_B") (class "Default")
      (node (ref "J6") (pin "73") (pinfunction "73_73") (pintype "passive"))
    )
    (net (code "262") (name "SD1_STROBE") (class "Default")
      (node (ref "J6") (pin "71") (pinfunction "71_71") (pintype "passive"))
    )
    (net (code "263") (name "SD2_CLK") (class "Default")
      (node (ref "J3") (pin "96") (pinfunction "96_96") (pintype "passive"))
    )
    (net (code "264") (name "SD2_CMD") (class "Default")
      (node (ref "J3") (pin "98") (pinfunction "98_98") (pintype "passive"))
    )
    (net (code "265") (name "SD2_DATA0") (class "Default")
      (node (ref "J3") (pin "91") (pinfunction "91_91") (pintype "passive"))
    )
    (net (code "266") (name "SD2_DATA1") (class "Default")
      (node (ref "J3") (pin "93") (pinfunction "93_93") (pintype "passive"))
    )
    (net (code "267") (name "SD2_DATA2") (class "Default")
      (node (ref "J3") (pin "95") (pinfunction "95_95") (pintype "passive"))
    )
    (net (code "268") (name "SD2_DATA3") (class "Default")
      (node (ref "J3") (pin "97") (pinfunction "97_97") (pintype "passive"))
    )
    (net (code "269") (name "SD2_RESET_B") (class "Default")
      (node (ref "J3") (pin "35") (pinfunction "35_35") (pintype "passive"))
    )
    (net (code "270") (name "SD2_WP") (class "Default")
      (node (ref "J3") (pin "92") (pinfunction "92_92") (pintype "passive"))
    )
    (net (code "271") (name "SD2_nCD") (class "Default")
      (node (ref "J3") (pin "94") (pinfunction "94_94") (pintype "passive"))
    )
    (net (code "272") (name "SPDIF_EXT_CLK") (class "Default")
      (node (ref "J5") (pin "76") (pinfunction "76_76") (pintype "passive"))
    )
    (net (code "273") (name "SPDIF_RX") (class "Default")
      (node (ref "J5") (pin "78") (pinfunction "78_78") (pintype "passive"))
    )
    (net (code "274") (name "SPDIF_TX") (class "Default")
      (node (ref "J5") (pin "88") (pinfunction "88_88") (pintype "passive"))
    )
    (net (code "275") (name "SYS_nRST") (class "Default")
      (node (ref "J5") (pin "43") (pinfunction "43_43") (pintype "passive"))
    )
    (net (code "276") (name "UART1_RXD") (class "Default")
      (node (ref "J5") (pin "54") (pinfunction "54_54") (pintype "passive"))
    )
    (net (code "277") (name "UART1_TXD") (class "Default")
      (node (ref "J3") (pin "6") (pinfunction "6_6") (pintype "passive"))
    )
    (net (code "278") (name "UART2_RXD") (class "Default")
      (node (ref "J5") (pin "64") (pinfunction "64_64") (pintype "passive"))
    )
    (net (code "279") (name "UART2_TXD") (class "Default")
      (node (ref "J3") (pin "12") (pinfunction "12_12") (pintype "passive"))
    )
    (net (code "280") (name "UART3_RXD") (class "Default")
      (node (ref "J5") (pin "56") (pinfunction "56_56") (pintype "passive"))
    )
    (net (code "281") (name "UART3_TXD") (class "Default")
      (node (ref "J3") (pin "8") (pinfunction "8_8") (pintype "passive"))
    )
    (net (code "282") (name "UART4_RXD") (class "Default")
      (node (ref "J3") (pin "14") (pinfunction "14_14") (pintype "passive"))
    )
    (net (code "283") (name "UART4_TXD") (class "Default")
      (node (ref "J3") (pin "18") (pinfunction "18_18") (pintype "passive"))
    )
    (net (code "284") (name "USB1_D_N") (class "Default")
      (node (ref "J4") (pin "36") (pinfunction "36_36") (pintype "passive"))
    )
    (net (code "285") (name "USB1_D_P") (class "Default")
      (node (ref "J4") (pin "38") (pinfunction "38_38") (pintype "passive"))
    )
    (net (code "286") (name "USB1_RX_N") (class "Default")
      (node (ref "J4") (pin "29") (pinfunction "29_29") (pintype "passive"))
    )
    (net (code "287") (name "USB1_RX_P") (class "Default")
      (node (ref "J4") (pin "31") (pinfunction "31_31") (pintype "passive"))
    )
    (net (code "288") (name "USB1_TX_N") (class "Default")
      (node (ref "J4") (pin "35") (pinfunction "35_35") (pintype "passive"))
    )
    (net (code "289") (name "USB1_TX_P") (class "Default")
      (node (ref "J4") (pin "37") (pinfunction "37_37") (pintype "passive"))
    )
    (net (code "290") (name "USB1_VBUS_3V3") (class "Default")
      (node (ref "J4") (pin "44") (pinfunction "44_44") (pintype "passive"))
    )
    (net (code "291") (name "USB2_D_N") (class "Default")
      (node (ref "J4") (pin "54") (pinfunction "54_54") (pintype "passive"))
    )
    (net (code "292") (name "USB2_D_P") (class "Default")
      (node (ref "J4") (pin "56") (pinfunction "56_56") (pintype "passive"))
    )
    (net (code "293") (name "USB2_RX_N") (class "Default")
      (node (ref "J4") (pin "41") (pinfunction "41_41") (pintype "passive"))
    )
    (net (code "294") (name "USB2_RX_P") (class "Default")
      (node (ref "J4") (pin "43") (pinfunction "43_43") (pintype "passive"))
    )
    (net (code "295") (name "USB2_TX_N") (class "Default")
      (node (ref "J4") (pin "47") (pinfunction "47_47") (pintype "passive"))
    )
    (net (code "296") (name "USB2_TX_P") (class "Default")
      (node (ref "J4") (pin "49") (pinfunction "49_49") (pintype "passive"))
    )
    (net (code "297") (name "USB2_VBUS_3V3") (class "Default")
      (node (ref "J4") (pin "50") (pinfunction "50_50") (pintype "passive"))
    )
    (net (code "298") (name "VDD_1V8") (class "Default")
      (node (ref "J5") (pin "29") (pinfunction "29_29") (pintype "passive"))
      (node (ref "J5") (pin "31") (pinfunction "31_31") (pintype "passive"))
      (node (ref "J5") (pin "33") (pinfunction "33_33") (pintype "passive"))
      (node (ref "J5") (pin "35") (pinfunction "35_35") (pintype "passive"))
      (node (ref "J5") (pin "37") (pinfunction "37_37") (pintype "passive"))
      (node (ref "J5") (pin "39") (pinfunction "39_39") (pintype "passive"))
    )
    (net (code "299") (name "VDD_3V3") (class "Default")
      (node (ref "J5") (pin "30") (pinfunction "30_30") (pintype "passive"))
      (node (ref "J5") (pin "32") (pinfunction "32_32") (pintype "passive"))
      (node (ref "J5") (pin "34") (pinfunction "34_34") (pintype "passive"))
      (node (ref "J5") (pin "36") (pinfunction "36_36") (pintype "passive"))
      (node (ref "J5") (pin "38") (pinfunction "38_38") (pintype "passive"))
      (node (ref "J5") (pin "40") (pinfunction "40_40") (pintype "passive"))
    )
    (net (code "300") (name "VSD_3V3") (class "Default")
      (node (ref "J5") (pin "42") (pinfunction "42_42") (pintype "passive"))
      (node (ref "J5") (pin "44") (pinfunction "44_44") (pintype "passive"))
      (node (ref "J5") (pin "46") (pinfunction "46_46") (pintype "passive"))
    )
    (net (code "301") (name "VSYS_5V") (class "Default")
      (node (ref "J5") (pin "1") (pinfunction "1_1") (pintype "passive"))
      (node (ref "J5") (pin "10") (pinfunction "10_10") (pintype "passive"))
      (node (ref "J5") (pin "11") (pinfunction "11_11") (pintype "passive"))
      (node (ref "J5") (pin "12") (pinfunction "12_12") (pintype "passive"))
      (node (ref "J5") (pin "2") (pinfunction "2_2") (pintype "passive"))
      (node (ref "J5") (pin "3") (pinfunction "3_3") (pintype "passive"))
      (node (ref "J5") (pin "4") (pinfunction "4_4") (pintype "passive"))
      (node (ref "J5") (pin "5") (pinfunction "5_5") (pintype "passive"))
      (node (ref "J5") (pin "6") (pinfunction "6_6") (pintype "passive"))
      (node (ref "J5") (pin "7") (pinfunction "7_7") (pintype "passive"))
      (node (ref "J5") (pin "8") (pinfunction "8_8") (pintype "passive"))
      (node (ref "J5") (pin "9") (pinfunction "9_9") (pintype "passive"))
    )
    (net (code "302") (name "unconnected-(J3-Pad76)") (class "Default")
      (node (ref "J3") (pin "76") (pinfunction "76_76") (pintype "passive+no_connect"))
    )
    (net (code "303") (name "unconnected-(J3-Pad78)") (class "Default")
      (node (ref "J3") (pin "78") (pinfunction "78_78") (pintype "passive+no_connect"))
    )
    (net (code "304") (name "unconnected-(J4-Pad1)") (class "Default")
      (node (ref "J4") (pin "1") (pinfunction "1_1") (pintype "passive+no_connect"))
    )
    (net (code "305") (name "unconnected-(J4-Pad2)") (class "Default")
      (node (ref "J4") (pin "2") (pinfunction "2_2") (pintype "passive+no_connect"))
    )
    (net (code "306") (name "unconnected-(J4-Pad3)") (class "Default")
      (node (ref "J4") (pin "3") (pinfunction "3_3") (pintype "passive+no_connect"))
    )
    (net (code "307") (name "unconnected-(J4-Pad4)") (class "Default")
      (node (ref "J4") (pin "4") (pinfunction "4_4") (pintype "passive+no_connect"))
    )
    (net (code "308") (name "unconnected-(J4-Pad5)") (class "Default")
      (node (ref "J4") (pin "5") (pinfunction "5_5") (pintype "passive+no_connect"))
    )
    (net (code "309") (name "unconnected-(J4-Pad6)") (class "Default")
      (node (ref "J4") (pin "6") (pinfunction "6_6") (pintype "passive+no_connect"))
    )
    (net (code "310") (name "unconnected-(J4-Pad42)") (class "Default")
      (node (ref "J4") (pin "42") (pinfunction "42_42") (pintype "passive+no_connect"))
    )
    (net (code "311") (name "unconnected-(J4-Pad48)") (class "Default")
      (node (ref "J4") (pin "48") (pinfunction "48_48") (pintype "passive+no_connect"))
    )
    (net (code "312") (name "unconnected-(J5-Pad48)") (class "Default")
      (node (ref "J5") (pin "48") (pinfunction "48_48") (pintype "passive+no_connect"))
    )
    (net (code "313") (name "unconnected-(J5-Pad52)") (class "Default")
      (node (ref "J5") (pin "52") (pinfunction "52_52") (pintype "passive+no_connect"))
    )
    (net (code "314") (name "unconnected-(J5-Pad63)") (class "Default")
      (node (ref "J5") (pin "63") (pinfunction "63_63") (pintype "passive+no_connect"))
    )
    (net (code "315") (name "unconnected-(J5-Pad71)") (class "Default")
      (node (ref "J5") (pin "71") (pinfunction "71_71") (pintype "passive+no_connect"))
    )
    (net (code "316") (name "unconnected-(J5-Pad72)") (class "Default")
      (node (ref "J5") (pin "72") (pinfunction "72_72") (pintype "passive+no_connect"))
    )
    (net (code "317") (name "unconnected-(J5-Pad73)") (class "Default")
      (node (ref "J5") (pin "73") (pinfunction "73_73") (pintype "passive+no_connect"))
    )
    (net (code "318") (name "unconnected-(J5-Pad74)") (class "Default")
      (node (ref "J5") (pin "74") (pinfunction "74_74") (pintype "passive+no_connect"))
    )
    (net (code "319") (name "unconnected-(J5-Pad86)") (class "Default")
      (node (ref "J5") (pin "86") (pinfunction "86_86") (pintype "passive+no_connect"))
    )
    (net (code "320") (name "unconnected-(J5-Pad87)") (class "Default")
      (node (ref "J5") (pin "87") (pinfunction "87_87") (pintype "passive+no_connect"))
    )
    (net (code "321") (name "unconnected-(J6-Pad34)") (class "Default")
      (node (ref "J6") (pin "34") (pinfunction "34_34") (pintype "passive+no_connect"))
    )
    (net (code "322") (name "unconnected-(J6-Pad36)") (class "Default")
      (node (ref "J6") (pin "36") (pinfunction "36_36") (pintype "passive+no_connect"))
    )
    (net (code "323") (name "unconnected-(J6-Pad38)") (class "Default")
      (node (ref "J6") (pin "38") (pinfunction "38_38") (pintype "passive+no_connect"))
    )
    (net (code "324") (name "unconnected-(J6-Pad42)") (class "Default")
      (node (ref "J6") (pin "42") (pinfunction "42_42") (pintype "passive+no_connect"))
    )
    (net (code "325") (name "unconnected-(J6-Pad44)") (class "Default")
      (node (ref "J6") (pin "44") (pinfunction "44_44") (pintype "passive+no_connect"))
    )
    (net (code "326") (name "unconnected-(J6-Pad48)") (class "Default")
      (node (ref "J6") (pin "48") (pinfunction "48_48") (pintype "passive+no_connect"))
    )
    (net (code "327") (name "unconnected-(J6-Pad54)") (class "Default")
      (node (ref "J6") (pin "54") (pinfunction "54_54") (pintype "passive"))
    )
    (net (code "328") (name "unconnected-(J6-Pad56)") (class "Default")
      (node (ref "J6") (pin "56") (pinfunction "56_56") (pintype "passive+no_connect"))
    )
    (net (code "329") (name "unconnected-(J6-Pad58)") (class "Default")
      (node (ref "J6") (pin "58") (pinfunction "58_58") (pintype "passive+no_connect"))
    )
    (net (code "330") (name "unconnected-(J6-Pad62)") (class "Default")
      (node (ref "J6") (pin "62") (pinfunction "62_62") (pintype "passive+no_connect"))
    )
    (net (code "331") (name "unconnected-(J6-Pad64)") (class "Default")
      (node (ref "J6") (pin "64") (pinfunction "64_64") (pintype "passive+no_connect"))
    )
    (net (code "332") (name "unconnected-(J6-Pad66)") (class "Default")
      (node (ref "J6") (pin "66") (pinfunction "66_66") (pintype "passive+no_connect"))
    )
    (net (code "333") (name "unconnected-(J6-Pad68)") (class "Default")
      (node (ref "J6") (pin "68") (pinfunction "68_68") (pintype "passive+no_connect"))
    )
    (net (code "334") (name "unconnected-(J6-Pad72)") (class "Default")
      (node (ref "J6") (pin "72") (pinfunction "72_72") (pintype "passive+no_connect"))
    )
    (net (code "335") (name "unconnected-(J6-Pad82)") (class "Default")
      (node (ref "J6") (pin "82") (pinfunction "82_82") (pintype "passive+no_connect"))
    )
  )
)
